# Bridge.net
KiCad netlist of a schematic drawn in Altium Designer
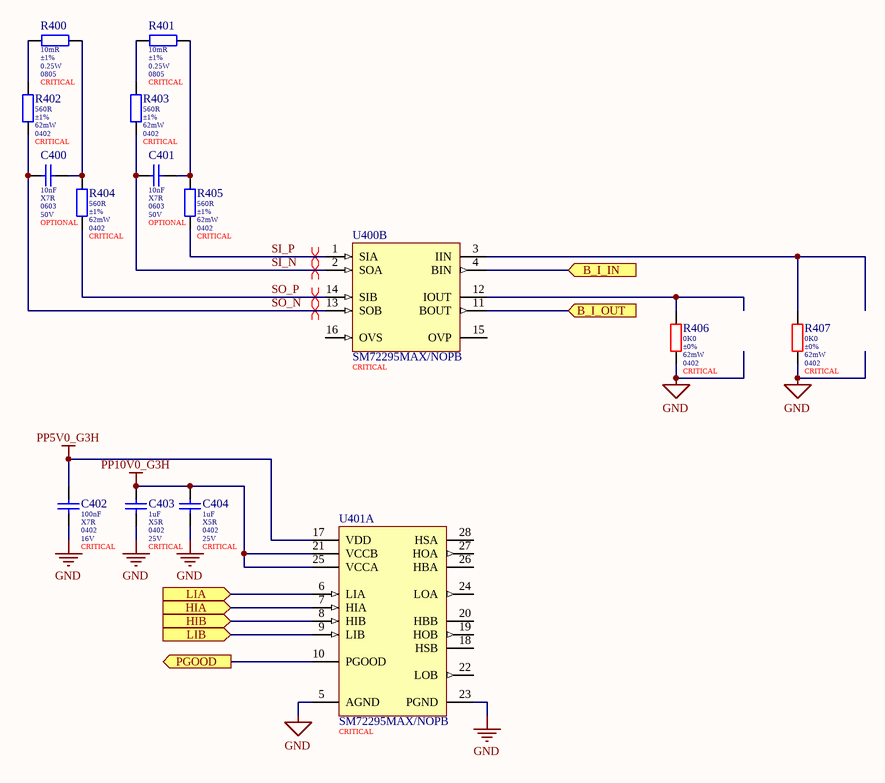
[diagram p0: Bridge.SchDoc]

(export (version "E")
  (design (tool "Eeschema 10.0.6"))
  (components
    (comp (ref "C400")
      (value "10nF")
      (footprint "0603_080")
      (description "MLCC 10nF 0603 50V X7R ±10%")
      (fields
        (field (name "DIELECTRIC") "X7R")
        (field (name "PACKAGE") "0603")
        (field (name "VOLTAGE") "50V")
        (field (name "POPULATE") "OPTIONAL")
        (field (name "LCSC PART NUMBER") "C57112")
        (field (name "TOLERANCE") "±10%")
        (field (name "SOURCE") "MLCCs Guangdong.SchLib")
      )
      (libsource (lib "UCT - University of Cape Town") (part "Symbol"))
    )
    (comp (ref "C401")
      (value "10nF")
      (footprint "0603_080")
      (description "MLCC 10nF 0603 50V X7R ±10%")
      (fields
        (field (name "DIELECTRIC") "X7R")
        (field (name "PACKAGE") "0603")
        (field (name "VOLTAGE") "50V")
        (field (name "POPULATE") "OPTIONAL")
        (field (name "LCSC PART NUMBER") "C57112")
        (field (name "TOLERANCE") "±10%")
        (field (name "SOURCE") "MLCCs Guangdong.SchLib")
      )
      (libsource (lib "UCT - University of Cape Town") (part "Symbol"))
    )
    (comp (ref "C402")
      (value "100nF")
      (footprint "0402_050_5_N")
      (description "MLCC 100nF 0402 16V X7R ±10%")
      (fields
        (field (name "DIELECTRIC") "X7R")
        (field (name "PACKAGE") "0402")
        (field (name "VOLTAGE") "16V")
        (field (name "POPULATE") "CRITICAL")
        (field (name "TOLERANCE") "±10%")
        (field (name "LCSC PART NUMBER") "C1525")
      )
      (libsource (lib "UCT - University of Cape Town") (part "Symbol"))
    )
    (comp (ref "C403")
      (value "1uF")
      (footprint "0402_050_5_N")
      (description "MLCC 1uF 0402 25V X5R ±10%")
      (fields
        (field (name "DIELECTRIC") "X5R")
        (field (name "PACKAGE") "0402")
        (field (name "VOLTAGE") "25V")
        (field (name "POPULATE") "CRITICAL")
        (field (name "TOLERANCE") "±10%")
        (field (name "LCSC PART NUMBER") "C52923")
      )
      (libsource (lib "UCT - University of Cape Town") (part "Symbol"))
    )
    (comp (ref "C404")
      (value "1uF")
      (footprint "0402_050_5_N")
      (description "MLCC 1uF 0402 25V X5R ±10%")
      (fields
        (field (name "DIELECTRIC") "X5R")
        (field (name "PACKAGE") "0402")
        (field (name "VOLTAGE") "25V")
        (field (name "POPULATE") "CRITICAL")
        (field (name "TOLERANCE") "±10%")
        (field (name "LCSC PART NUMBER") "C52923")
      )
      (libsource (lib "UCT - University of Cape Town") (part "Symbol"))
    )
    (comp (ref "R400")
      (value "10mR")
      (footprint "0805")
      (description "Resistor 10mR 0805 ±1% Thick Film Uniroyal")
      (fields
        (field (name "TOLERANCE") "±1%")
        (field (name "POWER") "0.25W")
        (field (name "PACKAGE") "0805")
        (field (name "POPULATE") "CRITICAL")
        (field (name "LCSC PART NUMBER") "C270927")
        (field (name "Comment") "0805W4F100MT5E")
      )
      (libsource (lib "") (part "Symbol_1"))
    )
    (comp (ref "R401")
      (value "10mR")
      (footprint "0805")
      (description "Resistor 10mR 0805 ±1% Thick Film Uniroyal")
      (fields
        (field (name "TOLERANCE") "±1%")
        (field (name "POWER") "0.25W")
        (field (name "PACKAGE") "0805")
        (field (name "POPULATE") "CRITICAL")
        (field (name "LCSC PART NUMBER") "C270927")
        (field (name "Comment") "0805W4F100MT5E")
      )
      (libsource (lib "") (part "Symbol_1"))
    )
    (comp (ref "R402")
      (value "560R")
      (footprint "0402")
      (description "Resistor 560R 0402 ±1% Thick Film Uniroyal")
      (fields
        (field (name "TOLERANCE") "±1%")
        (field (name "POWER") "62mW")
        (field (name "PACKAGE") "0402")
        (field (name "POPULATE") "CRITICAL")
        (field (name "LCSC PART NUMBER") "C25172")
        (field (name "Comment") "0402WGJ0561TCE")
      )
      (libsource (lib "") (part "Symbol_1"))
    )
    (comp (ref "R403")
      (value "560R")
      (footprint "0402")
      (description "Resistor 560R 0402 ±1% Thick Film Uniroyal")
      (fields
        (field (name "TOLERANCE") "±1%")
        (field (name "POWER") "62mW")
        (field (name "PACKAGE") "0402")
        (field (name "POPULATE") "CRITICAL")
        (field (name "LCSC PART NUMBER") "C25172")
        (field (name "Comment") "0402WGJ0561TCE")
      )
      (libsource (lib "") (part "Symbol_1"))
    )
    (comp (ref "R404")
      (value "560R")
      (footprint "0402")
      (description "Resistor 560R 0402 ±1% Thick Film Uniroyal")
      (fields
        (field (name "TOLERANCE") "±1%")
        (field (name "POWER") "62mW")
        (field (name "PACKAGE") "0402")
        (field (name "POPULATE") "CRITICAL")
        (field (name "LCSC PART NUMBER") "C25172")
        (field (name "Comment") "0402WGJ0561TCE")
      )
      (libsource (lib "") (part "Symbol_1"))
    )
    (comp (ref "R405")
      (value "560R")
      (footprint "0402")
      (description "Resistor 560R 0402 ±1% Thick Film Uniroyal")
      (fields
        (field (name "TOLERANCE") "±1%")
        (field (name "POWER") "62mW")
        (field (name "PACKAGE") "0402")
        (field (name "POPULATE") "CRITICAL")
        (field (name "LCSC PART NUMBER") "C25172")
        (field (name "Comment") "0402WGJ0561TCE")
      )
      (libsource (lib "") (part "Symbol_1"))
    )
    (comp (ref "R406")
      (value "0K0")
      (footprint "0402")
      (description "Generic 0402 Ressitor")
      (fields
        (field (name "TOLERANCE") "±0%")
        (field (name "POWER") "62mW")
        (field (name "PACKAGE") "0402")
        (field (name "POPULATE") "CRITICAL")
        (field (name "Comment") "Resistor Generic 0402")
      )
      (libsource (lib "") (part "Symbol_1"))
    )
    (comp (ref "R407")
      (value "0K0")
      (footprint "0402")
      (description "Generic 0402 Ressitor")
      (fields
        (field (name "TOLERANCE") "±0%")
        (field (name "POWER") "62mW")
        (field (name "PACKAGE") "0402")
        (field (name "POPULATE") "CRITICAL")
        (field (name "Comment") "Resistor Generic 0402")
      )
      (libsource (lib "") (part "Symbol_1"))
    )
    (comp (ref "U400")
      (value "SM72295MAX/NOPB")
      (footprint "DW0028A_L")
      (description "Photovoltaic Full BridgeDriver 3A Non-Inv 28-Pin SOIC W T/R")
      (fields (field (name "PLACEMENT") "CRITICAL"))
      (libsource (lib "UCT - University of Cape Town") (part "IN-BDRV-SM72295-IL28"))
    )
    (comp (ref "U401")
      (value "SM72295MAX/NOPB")
      (footprint "DW0028A_L")
      (description "Photovoltaic Full BridgeDriver 3A Non-Inv 28-Pin SOIC W T/R")
      (fields (field (name "PLACEMENT") "CRITICAL"))
      (libsource (lib "") (part "IN-BDRV-SM72295-IL28_1"))
    )
  )
  (nets
    (net (code "1") (name "/B_I_IN") (class "Default")
      (node (ref "U400") (pin "4") (pinfunction "BIN_4") (pintype "output"))
    )
    (net (code "2") (name "/B_I_OUT") (class "Default")
      (node (ref "U400") (pin "11") (pinfunction "BOUT_11") (pintype "output"))
    )
    (net (code "3") (name "/HIA") (class "Default")
      (node (ref "U401") (pin "7") (pinfunction "HIA_7") (pintype "input"))
    )
    (net (code "4") (name "/HIB") (class "Default")
      (node (ref "U401") (pin "8") (pinfunction "HIB_8") (pintype "input"))
    )
    (net (code "5") (name "/LIA") (class "Default")
      (node (ref "U401") (pin "6") (pinfunction "LIA_6") (pintype "input"))
    )
    (net (code "6") (name "/LIB") (class "Default")
      (node (ref "U401") (pin "9") (pinfunction "LIB_9") (pintype "input"))
    )
    (net (code "7") (name "/PGOOD") (class "Default")
      (node (ref "U401") (pin "10") (pinfunction "PGOOD_10") (pintype "open_collector"))
    )
    (net (code "8") (name "/SI_N") (class "Default")
      (node (ref "C401") (pin "1") (pinfunction "1_1") (pintype "passive"))
      (node (ref "R403") (pin "2") (pinfunction "2_2") (pintype "passive"))
      (node (ref "U400") (pin "2") (pinfunction "SOA_2") (pintype "input"))
    )
    (net (code "9") (name "/SI_P") (class "Default")
      (node (ref "R405") (pin "2") (pinfunction "2_2") (pintype "passive"))
      (node (ref "U400") (pin "1") (pinfunction "SIA_1") (pintype "input"))
    )
    (net (code "10") (name "/SO_N") (class "Default")
      (node (ref "C400") (pin "1") (pinfunction "1_1") (pintype "passive"))
      (node (ref "R402") (pin "2") (pinfunction "2_2") (pintype "passive"))
      (node (ref "U400") (pin "13") (pinfunction "SOB_13") (pintype "input"))
    )
    (net (code "11") (name "/SO_P") (class "Default")
      (node (ref "R404") (pin "2") (pinfunction "2_2") (pintype "passive"))
      (node (ref "U400") (pin "14") (pinfunction "SIB_14") (pintype "input"))
    )
    (net (code "12") (name "GND") (class "Default")
      (node (ref "C402") (pin "2") (pinfunction "2_2") (pintype "passive"))
      (node (ref "C403") (pin "2") (pinfunction "2_2") (pintype "passive"))
      (node (ref "C404") (pin "2") (pinfunction "2_2") (pintype "passive"))
      (node (ref "R406") (pin "2") (pinfunction "2_2") (pintype "passive"))
      (node (ref "R407") (pin "2") (pinfunction "2_2") (pintype "passive"))
      (node (ref "U401") (pin "23") (pinfunction "PGND_23") (pintype "power_in"))
      (node (ref "U401") (pin "5") (pinfunction "AGND_5") (pintype "power_in"))
    )
    (net (code "13") (name "Net-(C400-Pad2)") (class "Default")
      (node (ref "C400") (pin "2") (pinfunction "2_2") (pintype "passive"))
      (node (ref "R400") (pin "2") (pinfunction "2_2") (pintype "passive"))
      (node (ref "R404") (pin "1") (pinfunction "1_1") (pintype "passive"))
    )
    (net (code "14") (name "Net-(C401-Pad2)") (class "Default")
      (node (ref "C401") (pin "2") (pinfunction "2_2") (pintype "passive"))
      (node (ref "R401") (pin "2") (pinfunction "2_2") (pintype "passive"))
      (node (ref "R405") (pin "1") (pinfunction "1_1") (pintype "passive"))
    )
    (net (code "15") (name "Net-(R400-Pad1)") (class "Default")
      (node (ref "R400") (pin "1") (pinfunction "1_1") (pintype "passive"))
      (node (ref "R402") (pin "1") (pinfunction "1_1") (pintype "passive"))
    )
    (net (code "16") (name "Net-(R401-Pad1)") (class "Default")
      (node (ref "R401") (pin "1") (pinfunction "1_1") (pintype "passive"))
      (node (ref "R403") (pin "1") (pinfunction "1_1") (pintype "passive"))
    )
    (net (code "17") (name "Net-(U400B-IIN)") (class "Default")
      (node (ref "R407") (pin "1") (pinfunction "1_1") (pintype "passive"))
      (node (ref "U400") (pin "3") (pinfunction "IIN_3") (pintype "passive"))
    )
    (net (code "18") (name "Net-(U400B-IOUT)") (class "Default")
      (node (ref "R406") (pin "1") (pinfunction "1_1") (pintype "passive"))
      (node (ref "U400") (pin "12") (pinfunction "IOUT_12") (pintype "passive"))
    )
    (net (code "19") (name "PP5V0_G3H") (class "Default")
      (node (ref "C402") (pin "1") (pinfunction "1_1") (pintype "passive"))
      (node (ref "U401") (pin "17") (pinfunction "VDD_17") (pintype "power_in"))
    )
    (net (code "20") (name "PP10V0_G3H") (class "Default")
      (node (ref "C403") (pin "1") (pinfunction "1_1") (pintype "passive"))
      (node (ref "C404") (pin "1") (pinfunction "1_1") (pintype "passive"))
      (node (ref "U401") (pin "21") (pinfunction "VCCB_21") (pintype "power_in"))
      (node (ref "U401") (pin "25") (pinfunction "VCCA_25") (pintype "power_in"))
    )
    (net (code "21") (name "unconnected-(U400B-OVP-Pad15)") (class "Default")
      (node (ref "U400") (pin "15") (pinfunction "OVP_15") (pintype "open_collector"))
    )
    (net (code "22") (name "unconnected-(U400B-OVS-Pad16)") (class "Default")
      (node (ref "U400") (pin "16") (pinfunction "OVS_16") (pintype "input"))
    )
    (net (code "23") (name "unconnected-(U401A-HBA-Pad26)") (class "Default")
      (node (ref "U401") (pin "26") (pinfunction "HBA_26") (pintype "passive"))
    )
    (net (code "24") (name "unconnected-(U401A-HBB-Pad20)") (class "Default")
      (node (ref "U401") (pin "20") (pinfunction "HBB_20") (pintype "passive"))
    )
    (net (code "25") (name "unconnected-(U401A-HOA-Pad27)") (class "Default")
      (node (ref "U401") (pin "27") (pinfunction "HOA_27") (pintype "output"))
    )
    (net (code "26") (name "unconnected-(U401A-HOB-Pad19)") (class "Default")
      (node (ref "U401") (pin "19") (pinfunction "HOB_19") (pintype "output"))
    )
    (net (code "27") (name "unconnected-(U401A-HSA-Pad28)") (class "Default")
      (node (ref "U401") (pin "28") (pinfunction "HSA_28") (pintype "passive"))
    )
    (net (code "28") (name "unconnected-(U401A-HSB-Pad18)") (class "Default")
      (node (ref "U401") (pin "18") (pinfunction "HSB_18") (pintype "passive"))
    )
    (net (code "29") (name "unconnected-(U401A-LOA-Pad24)") (class "Default")
      (node (ref "U401") (pin "24") (pinfunction "LOA_24") (pintype "output"))
    )
    (net (code "30") (name "unconnected-(U401A-LOB-Pad22)") (class "Default")
      (node (ref "U401") (pin "22") (pinfunction "LOB_22") (pintype "output"))
    )
  )
)
